# 9x_Connection_Board_A_v0_2.net
KiCad netlist of a schematic drawn in EAGLE
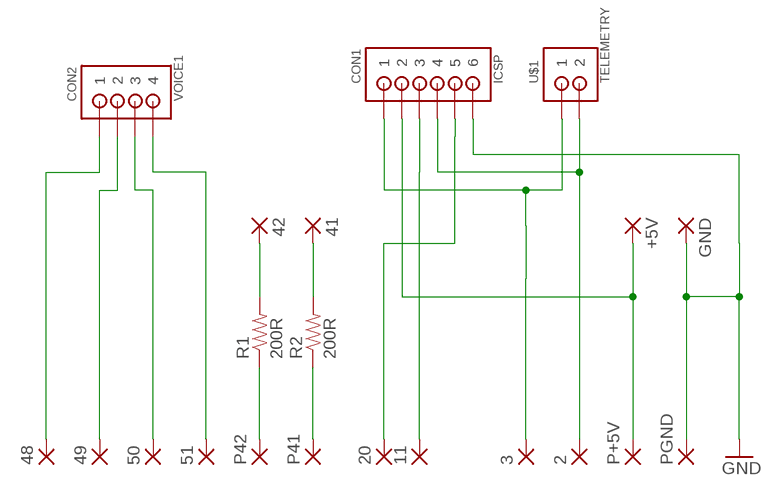
[diagram p0: schematic, sheet 1]

(export (version "E")
  (design (tool "Eeschema 10.0.6"))
  (components
    (comp (ref "+5V")
      (value "WIREPADSMD1,27-254")
      (footprint "eagle-import:SMD1,27-2,54")
      (libsource (lib "eagle-import") (part "WIREPADSMD1,27-254"))
    )
    (comp (ref "2")
      (value "WIREPADSMD1,27-254")
      (footprint "eagle-import:SMD1,27-2,54")
      (libsource (lib "eagle-import") (part "WIREPADSMD1,27-254"))
    )
    (comp (ref "3")
      (value "WIREPADSMD1,27-254")
      (footprint "eagle-import:SMD1,27-2,54")
      (libsource (lib "eagle-import") (part "WIREPADSMD1,27-254"))
    )
    (comp (ref "11")
      (value "WIREPADSMD1,27-254")
      (footprint "eagle-import:SMD1,27-2,54")
      (libsource (lib "eagle-import") (part "WIREPADSMD1,27-254"))
    )
    (comp (ref "20")
      (value "WIREPADSMD1,27-254")
      (footprint "eagle-import:SMD1,27-2,54")
      (libsource (lib "eagle-import") (part "WIREPADSMD1,27-254"))
    )
    (comp (ref "41")
      (value "WIREPADSMD1,27-254")
      (footprint "eagle-import:SMD1,27-2,54")
      (libsource (lib "eagle-import") (part "WIREPADSMD1,27-254"))
    )
    (comp (ref "42")
      (value "WIREPADSMD1,27-254")
      (footprint "eagle-import:SMD1,27-2,54")
      (libsource (lib "eagle-import") (part "WIREPADSMD1,27-254"))
    )
    (comp (ref "48")
      (value "WIREPADSMD1,27-254")
      (footprint "eagle-import:SMD1,27-2,54")
      (libsource (lib "eagle-import") (part "WIREPADSMD1,27-254"))
    )
    (comp (ref "49")
      (value "WIREPADSMD1,27-254")
      (footprint "eagle-import:SMD1,27-2,54")
      (libsource (lib "eagle-import") (part "WIREPADSMD1,27-254"))
    )
    (comp (ref "50")
      (value "WIREPADSMD1,27-254")
      (footprint "eagle-import:SMD1,27-2,54")
      (libsource (lib "eagle-import") (part "WIREPADSMD1,27-254"))
    )
    (comp (ref "51")
      (value "WIREPADSMD1,27-254")
      (footprint "eagle-import:SMD1,27-2,54")
      (libsource (lib "eagle-import") (part "WIREPADSMD1,27-254"))
    )
    (comp (ref "CON1")
      (value "ICSP")
      (footprint "eagle-import:B6B-ZR")
      (libsource (lib "eagle-import") (part "B6B-ZR"))
    )
    (comp (ref "CON2")
      (value "VOICE1")
      (footprint "eagle-import:B4B-ZR")
      (libsource (lib "eagle-import") (part "B4B-ZR"))
    )
    (comp (ref "GND")
      (value "WIREPADSMD1,27-254")
      (footprint "eagle-import:SMD1,27-2,54")
      (libsource (lib "eagle-import") (part "WIREPADSMD1,27-254"))
    )
    (comp (ref "P+5V")
      (value "WIREPADSMD1,27-254")
      (footprint "eagle-import:SMD1,27-2,54")
      (libsource (lib "eagle-import") (part "WIREPADSMD1,27-254"))
    )
    (comp (ref "P41")
      (value "WIREPADSMD1,27-254")
      (footprint "eagle-import:SMD1,27-2,54")
      (libsource (lib "eagle-import") (part "WIREPADSMD1,27-254"))
    )
    (comp (ref "P42")
      (value "WIREPADSMD1,27-254")
      (footprint "eagle-import:SMD1,27-2,54")
      (libsource (lib "eagle-import") (part "WIREPADSMD1,27-254"))
    )
    (comp (ref "PGND")
      (value "WIREPADSMD1,27-254")
      (footprint "eagle-import:SMD1,27-2,54")
      (libsource (lib "eagle-import") (part "WIREPADSMD1,27-254"))
    )
    (comp (ref "R1")
      (value "200R")
      (footprint "eagle-import:0805")
      (libsource (lib "eagle-import") (part "RESISTOR0805-RES"))
    )
    (comp (ref "R2")
      (value "200R")
      (footprint "eagle-import:0805")
      (libsource (lib "eagle-import") (part "RESISTOR0805-RES"))
    )
    (comp (ref "U$1")
      (value "TELEMETRY")
      (footprint "eagle-import:B2B-ZR")
      (libsource (lib "eagle-import") (part "B2B-ZR"))
    )
  )
  (nets
    (net (code "1") (name "GND") (class "Default")
      (node (ref "CON1") (pin "6") (pinfunction "6_6") (pintype "bidirectional"))
      (node (ref "GND") (pin "1") (pinfunction "P_1") (pintype "passive"))
      (node (ref "PGND") (pin "1") (pinfunction "P_1") (pintype "passive"))
    )
    (net (code "2") (name "Net-(+5V-P)") (class "Default")
      (node (ref "+5V") (pin "1") (pinfunction "P_1") (pintype "passive"))
      (node (ref "CON1") (pin "2") (pinfunction "2_2") (pintype "bidirectional"))
      (node (ref "P+5V") (pin "1") (pinfunction "P_1") (pintype "passive"))
    )
    (net (code "3") (name "Net-(2-P)") (class "Default")
      (node (ref "2") (pin "1") (pinfunction "P_1") (pintype "passive"))
      (node (ref "CON1") (pin "4") (pinfunction "4_4") (pintype "bidirectional"))
      (node (ref "U$1") (pin "2") (pinfunction "2_2") (pintype "bidirectional"))
    )
    (net (code "4") (name "Net-(3-P)") (class "Default")
      (node (ref "3") (pin "1") (pinfunction "P_1") (pintype "passive"))
      (node (ref "CON1") (pin "1") (pinfunction "1_1") (pintype "bidirectional"))
      (node (ref "U$1") (pin "1") (pinfunction "1_1") (pintype "bidirectional"))
    )
    (net (code "5") (name "Net-(11-P)") (class "Default")
      (node (ref "11") (pin "1") (pinfunction "P_1") (pintype "passive"))
      (node (ref "CON1") (pin "3") (pinfunction "3_3") (pintype "bidirectional"))
    )
    (net (code "6") (name "Net-(20-P)") (class "Default")
      (node (ref "20") (pin "1") (pinfunction "P_1") (pintype "passive"))
      (node (ref "CON1") (pin "5") (pinfunction "5_5") (pintype "bidirectional"))
    )
    (net (code "7") (name "Net-(41-P)") (class "Default")
      (node (ref "41") (pin "1") (pinfunction "P_1") (pintype "passive"))
      (node (ref "R2") (pin "2") (pinfunction "2_2") (pintype "passive"))
    )
    (net (code "8") (name "Net-(42-P)") (class "Default")
      (node (ref "42") (pin "1") (pinfunction "P_1") (pintype "passive"))
      (node (ref "R1") (pin "2") (pinfunction "2_2") (pintype "passive"))
    )
    (net (code "9") (name "Net-(48-P)") (class "Default")
      (node (ref "48") (pin "1") (pinfunction "P_1") (pintype "passive"))
      (node (ref "CON2") (pin "1") (pinfunction "1_1") (pintype "bidirectional"))
    )
    (net (code "10") (name "Net-(49-P)") (class "Default")
      (node (ref "49") (pin "1") (pinfunction "P_1") (pintype "passive"))
      (node (ref "CON2") (pin "2") (pinfunction "2_2") (pintype "bidirectional"))
    )
    (net (code "11") (name "Net-(50-P)") (class "Default")
      (node (ref "50") (pin "1") (pinfunction "P_1") (pintype "passive"))
      (node (ref "CON2") (pin "3") (pinfunction "3_3") (pintype "bidirectional"))
    )
    (net (code "12") (name "Net-(51-P)") (class "Default")
      (node (ref "51") (pin "1") (pinfunction "P_1") (pintype "passive"))
      (node (ref "CON2") (pin "4") (pinfunction "4_4") (pintype "bidirectional"))
    )
    (net (code "13") (name "Net-(P41-P)") (class "Default")
      (node (ref "P41") (pin "1") (pinfunction "P_1") (pintype "passive"))
      (node (ref "R2") (pin "1") (pinfunction "1_1") (pintype "passive"))
    )
    (net (code "14") (name "Net-(P42-P)") (class "Default")
      (node (ref "P42") (pin "1") (pinfunction "P_1") (pintype "passive"))
      (node (ref "R1") (pin "1") (pinfunction "1_1") (pintype "passive"))
    )
  )
)
